# MISC.net
KiCad netlist of a schematic drawn in Altium Designer
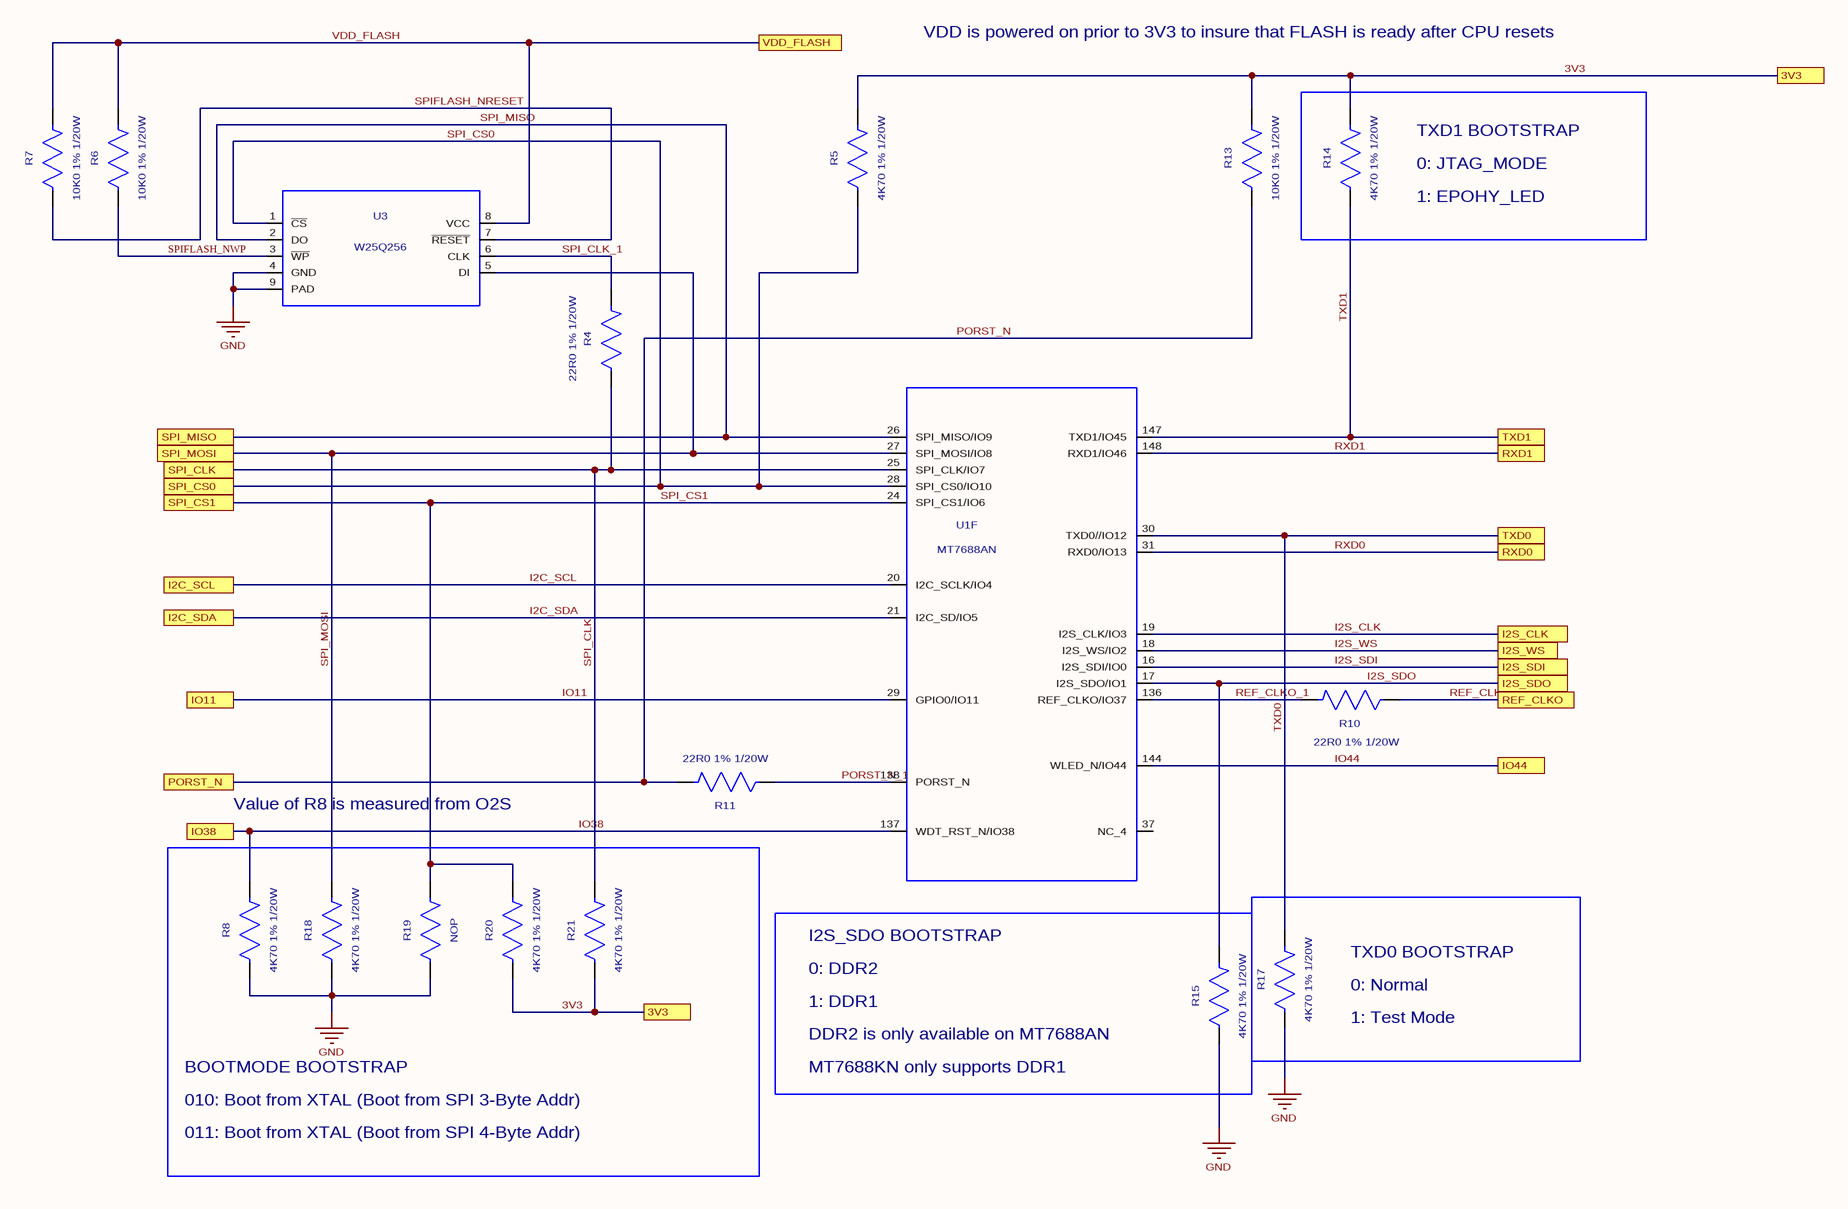
[diagram p0: MISC.SchDoc]

(export (version "E")
  (design (tool "Eeschema 10.0.6"))
  (components
    (comp (ref "R4")
      (value "22R0 1% 1/20W")
      (footprint "R0201")
      (description "RES 22 OHM 1% 1/20W 0201")
      (fields (field (name "MANUFACTURER") "Yageo") (field (name "PART NUMBER") "RC0201FR-0722RL"))
      (libsource (lib "NetworkModule") (part "RES0201-22R0"))
    )
    (comp (ref "R5")
      (value "4K70 1% 1/20W")
      (footprint "R0201")
      (description "RES 4.7K OHM 1% 1/20W 0201")
      (fields (field (name "MANUFACTURER") "Yageo") (field (name "PART NUMBER") "RC0201FR-074K7L"))
      (libsource (lib "NetworkModule") (part "RES0201-4K70"))
    )
    (comp (ref "R6")
      (value "10K0 1% 1/20W")
      (footprint "R0201")
      (description "RES SMD 10K OHM 1% 1/20W 0201")
      (fields (field (name "MANUFACTURER") "Yageo") (field (name "PART NUMBER") "RC0201FR-0710KP"))
      (libsource (lib "NetworkModule") (part "RES0201-10K0"))
    )
    (comp (ref "R7")
      (value "10K0 1% 1/20W")
      (footprint "R0201")
      (description "RES SMD 10K OHM 1% 1/20W 0201")
      (fields (field (name "MANUFACTURER") "Yageo") (field (name "PART NUMBER") "RC0201FR-0710KP"))
      (libsource (lib "NetworkModule") (part "RES0201-10K0"))
    )
    (comp (ref "R8")
      (value "4K70 1% 1/20W")
      (footprint "R0201")
      (description "RES 4.7K OHM 1% 1/20W 0201")
      (fields (field (name "MANUFACTURER") "Yageo") (field (name "PART NUMBER") "RC0201FR-074K7L"))
      (libsource (lib "NetworkModule") (part "RES0201-4K70"))
    )
    (comp (ref "R10")
      (value "22R0 1% 1/20W")
      (footprint "R0201")
      (description "RES 22 OHM 1% 1/20W 0201")
      (fields (field (name "MANUFACTURER") "Yageo") (field (name "PART NUMBER") "RC0201FR-0722RL"))
      (libsource (lib "NetworkModule") (part "RES0201-22R0"))
    )
    (comp (ref "R11")
      (value "22R0 1% 1/20W")
      (footprint "R0201")
      (description "RES 22 OHM 1% 1/20W 0201")
      (fields (field (name "MANUFACTURER") "Yageo") (field (name "PART NUMBER") "RC0201FR-0722RL"))
      (libsource (lib "NetworkModule") (part "RES0201-22R0"))
    )
    (comp (ref "R13")
      (value "10K0 1% 1/20W")
      (footprint "R0201")
      (description "RES SMD 10K OHM 1% 1/20W 0201")
      (fields (field (name "MANUFACTURER") "Yageo") (field (name "PART NUMBER") "RC0201FR-0710KP"))
      (libsource (lib "NetworkModule") (part "RES0201-10K0"))
    )
    (comp (ref "R14")
      (value "4K70 1% 1/20W")
      (footprint "R0201")
      (description "RES 4.7K OHM 1% 1/20W 0201")
      (fields (field (name "MANUFACTURER") "Yageo") (field (name "PART NUMBER") "RC0201FR-074K7L"))
      (libsource (lib "NetworkModule") (part "RES0201-4K70"))
    )
    (comp (ref "R15")
      (value "4K70 1% 1/20W")
      (footprint "R0201")
      (description "RES 4.7K OHM 1% 1/20W 0201")
      (fields (field (name "MANUFACTURER") "Yageo") (field (name "PART NUMBER") "RC0201FR-074K7L"))
      (libsource (lib "NetworkModule") (part "RES0201-4K70"))
    )
    (comp (ref "R17")
      (value "4K70 1% 1/20W")
      (footprint "R0201")
      (description "RES 4.7K OHM 1% 1/20W 0201")
      (fields (field (name "MANUFACTURER") "Yageo") (field (name "PART NUMBER") "RC0201FR-074K7L"))
      (libsource (lib "NetworkModule") (part "RES0201-4K70"))
    )
    (comp (ref "R18")
      (value "4K70 1% 1/20W")
      (footprint "R0201")
      (description "RES 4.7K OHM 1% 1/20W 0201")
      (fields (field (name "MANUFACTURER") "Yageo") (field (name "PART NUMBER") "RC0201FR-074K7L"))
      (libsource (lib "NetworkModule") (part "RES0201-4K70"))
    )
    (comp (ref "R19")
      (value "NOP")
      (footprint "R0201_NOP")
      (fields (field (name "Comment") "RES0201-NOP"))
      (libsource (lib "NetworkModule") (part "RES0201-NOP"))
    )
    (comp (ref "R20")
      (value "4K70 1% 1/20W")
      (footprint "R0201")
      (description "RES 4.7K OHM 1% 1/20W 0201")
      (fields (field (name "MANUFACTURER") "Yageo") (field (name "PART NUMBER") "RC0201FR-074K7L"))
      (libsource (lib "NetworkModule") (part "RES0201-4K70"))
    )
    (comp (ref "R21")
      (value "4K70 1% 1/20W")
      (footprint "R0201")
      (description "RES 4.7K OHM 1% 1/20W 0201")
      (fields (field (name "MANUFACTURER") "Yageo") (field (name "PART NUMBER") "RC0201FR-074K7L"))
      (libsource (lib "NetworkModule") (part "RES0201-4K70"))
    )
    (comp (ref "U1")
      (value "MT7688AN")
      (footprint "DR-QFN-128")
      (description "580Mhz 32bits Networking Processor")
      (fields (field (name "MANUFACTURER") "MediaTek Inc"))
      (libsource (lib "*") (part "MT7688AN"))
    )
    (comp (ref "U3")
      (value "W25Q256")
      (footprint "WIN_E-8_WIN")
      (description "IC FLASH 256MBIT SPI/QUAD 8WSON")
      (fields (field (name "PART NUMBER") "W25Q256JVEIQ"))
      (libsource (lib "NetworkModule") (part "W25Q256"))
    )
  )
  (nets
    (net (code "1") (name "/3V3") (class "Default")
      (node (ref "R13") (pin "2") (pinfunction "2_2") (pintype "passive"))
      (node (ref "R14") (pin "2") (pinfunction "2_2") (pintype "passive"))
      (node (ref "R20") (pin "1") (pinfunction "1_1") (pintype "passive"))
      (node (ref "R21") (pin "1") (pinfunction "1_1") (pintype "passive"))
      (node (ref "R5") (pin "2") (pinfunction "2_2") (pintype "passive"))
    )
    (net (code "2") (name "/I2C_SCL") (class "Default")
      (node (ref "U1") (pin "20") (pinfunction "I2C_SCLK/IO4_20") (pintype "passive"))
    )
    (net (code "3") (name "/I2C_SDA") (class "Default")
      (node (ref "U1") (pin "21") (pinfunction "I2C_SD/IO5_21") (pintype "passive"))
    )
    (net (code "4") (name "/I2S_CLK") (class "Default")
      (node (ref "U1") (pin "19") (pinfunction "I2S_CLK/IO3_19") (pintype "passive"))
    )
    (net (code "5") (name "/I2S_SDI") (class "Default")
      (node (ref "U1") (pin "16") (pinfunction "I2S_SDI/IO0_16") (pintype "passive"))
    )
    (net (code "6") (name "/I2S_SDO") (class "Default")
      (node (ref "R15") (pin "2") (pinfunction "2_2") (pintype "passive"))
      (node (ref "U1") (pin "17") (pinfunction "I2S_SDO/IO1_17") (pintype "passive"))
    )
    (net (code "7") (name "/I2S_WS") (class "Default")
      (node (ref "U1") (pin "18") (pinfunction "I2S_WS/IO2_18") (pintype "passive"))
    )
    (net (code "8") (name "/IO11") (class "Default")
      (node (ref "U1") (pin "29") (pinfunction "GPIO0/IO11_29") (pintype "passive"))
    )
    (net (code "9") (name "/IO38") (class "Default")
      (node (ref "R8") (pin "2") (pinfunction "2_2") (pintype "passive"))
      (node (ref "U1") (pin "137") (pinfunction "WDT_RST_N/IO38_137") (pintype "passive"))
    )
    (net (code "10") (name "/IO44") (class "Default")
      (node (ref "U1") (pin "144") (pinfunction "WLED_N/IO44_144") (pintype "passive"))
    )
    (net (code "11") (name "/PORST_N") (class "Default")
      (node (ref "R11") (pin "2") (pinfunction "2_2") (pintype "passive"))
      (node (ref "R13") (pin "1") (pinfunction "1_1") (pintype "passive"))
    )
    (net (code "12") (name "/PORST_N_1") (class "Default")
      (node (ref "R11") (pin "1") (pinfunction "1_1") (pintype "passive"))
      (node (ref "U1") (pin "138") (pinfunction "PORST_N_138") (pintype "passive"))
    )
    (net (code "13") (name "/REF_CLKO") (class "Default")
      (node (ref "R10") (pin "1") (pinfunction "1_1") (pintype "passive"))
    )
    (net (code "14") (name "/REF_CLKO_1") (class "Default")
      (node (ref "R10") (pin "2") (pinfunction "2_2") (pintype "passive"))
      (node (ref "U1") (pin "136") (pinfunction "REF_CLKO/IO37_136") (pintype "passive"))
    )
    (net (code "15") (name "/RXD0") (class "Default")
      (node (ref "U1") (pin "31") (pinfunction "RXD0/IO13_31") (pintype "passive"))
    )
    (net (code "16") (name "/RXD1") (class "Default")
      (node (ref "U1") (pin "148") (pinfunction "RXD1/IO46_148") (pintype "passive"))
    )
    (net (code "17") (name "/SPIFLASH_NRESET") (class "Default")
      (node (ref "R7") (pin "1") (pinfunction "1_1") (pintype "passive"))
      (node (ref "U3") (pin "7") (pinfunction "RESET_7") (pintype "passive"))
    )
    (net (code "18") (name "/SPIFLASH_NWP") (class "Default")
      (node (ref "R6") (pin "1") (pinfunction "1_1") (pintype "passive"))
      (node (ref "U3") (pin "3") (pinfunction "WP_3") (pintype "passive"))
    )
    (net (code "19") (name "/SPI_CLK") (class "Default")
      (node (ref "R21") (pin "2") (pinfunction "2_2") (pintype "passive"))
      (node (ref "R4") (pin "1") (pinfunction "1_1") (pintype "passive"))
      (node (ref "U1") (pin "25") (pinfunction "SPI_CLK/IO7_25") (pintype "passive"))
    )
    (net (code "20") (name "/SPI_CLK_1") (class "Default")
      (node (ref "R4") (pin "2") (pinfunction "2_2") (pintype "passive"))
      (node (ref "U3") (pin "6") (pinfunction "CLK_6") (pintype "passive"))
    )
    (net (code "21") (name "/SPI_CS0") (class "Default")
      (node (ref "R5") (pin "1") (pinfunction "1_1") (pintype "passive"))
      (node (ref "U1") (pin "28") (pinfunction "SPI_CS0/IO10_28") (pintype "passive"))
      (node (ref "U3") (pin "1") (pinfunction "CS_1") (pintype "passive"))
    )
    (net (code "22") (name "/SPI_CS1") (class "Default")
      (node (ref "R19") (pin "2") (pinfunction "2_2") (pintype "passive"))
      (node (ref "R20") (pin "2") (pinfunction "2_2") (pintype "passive"))
      (node (ref "U1") (pin "24") (pinfunction "SPI_CS1/IO6_24") (pintype "passive"))
    )
    (net (code "23") (name "/SPI_MISO") (class "Default")
      (node (ref "U1") (pin "26") (pinfunction "SPI_MISO/IO9_26") (pintype "passive"))
      (node (ref "U3") (pin "2") (pinfunction "DO_2") (pintype "passive"))
    )
    (net (code "24") (name "/SPI_MOSI") (class "Default")
      (node (ref "R18") (pin "2") (pinfunction "2_2") (pintype "passive"))
      (node (ref "U1") (pin "27") (pinfunction "SPI_MOSI/IO8_27") (pintype "passive"))
      (node (ref "U3") (pin "5") (pinfunction "DI_5") (pintype "passive"))
    )
    (net (code "25") (name "/TXD0") (class "Default")
      (node (ref "R17") (pin "2") (pinfunction "2_2") (pintype "passive"))
      (node (ref "U1") (pin "30") (pinfunction "TXD0//IO12_30") (pintype "passive"))
    )
    (net (code "26") (name "/TXD1") (class "Default")
      (node (ref "R14") (pin "1") (pinfunction "1_1") (pintype "passive"))
      (node (ref "U1") (pin "147") (pinfunction "TXD1/IO45_147") (pintype "passive"))
    )
    (net (code "27") (name "/VDD_FLASH") (class "Default")
      (node (ref "R6") (pin "2") (pinfunction "2_2") (pintype "passive"))
      (node (ref "R7") (pin "2") (pinfunction "2_2") (pintype "passive"))
      (node (ref "U3") (pin "8") (pinfunction "VCC_8") (pintype "passive"))
    )
    (net (code "28") (name "GND") (class "Default")
      (node (ref "R15") (pin "1") (pinfunction "1_1") (pintype "passive"))
      (node (ref "R17") (pin "1") (pinfunction "1_1") (pintype "passive"))
      (node (ref "R18") (pin "1") (pinfunction "1_1") (pintype "passive"))
      (node (ref "R19") (pin "1") (pinfunction "1_1") (pintype "passive"))
      (node (ref "R8") (pin "1") (pinfunction "1_1") (pintype "passive"))
      (node (ref "U3") (pin "4") (pinfunction "GND_4") (pintype "passive"))
      (node (ref "U3") (pin "9") (pinfunction "PAD_9") (pintype "passive"))
    )
    (net (code "29") (name "unconnected-(U1F-NC_4-Pad37)") (class "Default")
      (node (ref "U1") (pin "37") (pinfunction "NC_4_37") (pintype "passive"))
    )
  )
)
